# ArduinoMegaShield2.net
KiCad netlist of a schematic drawn in EAGLE
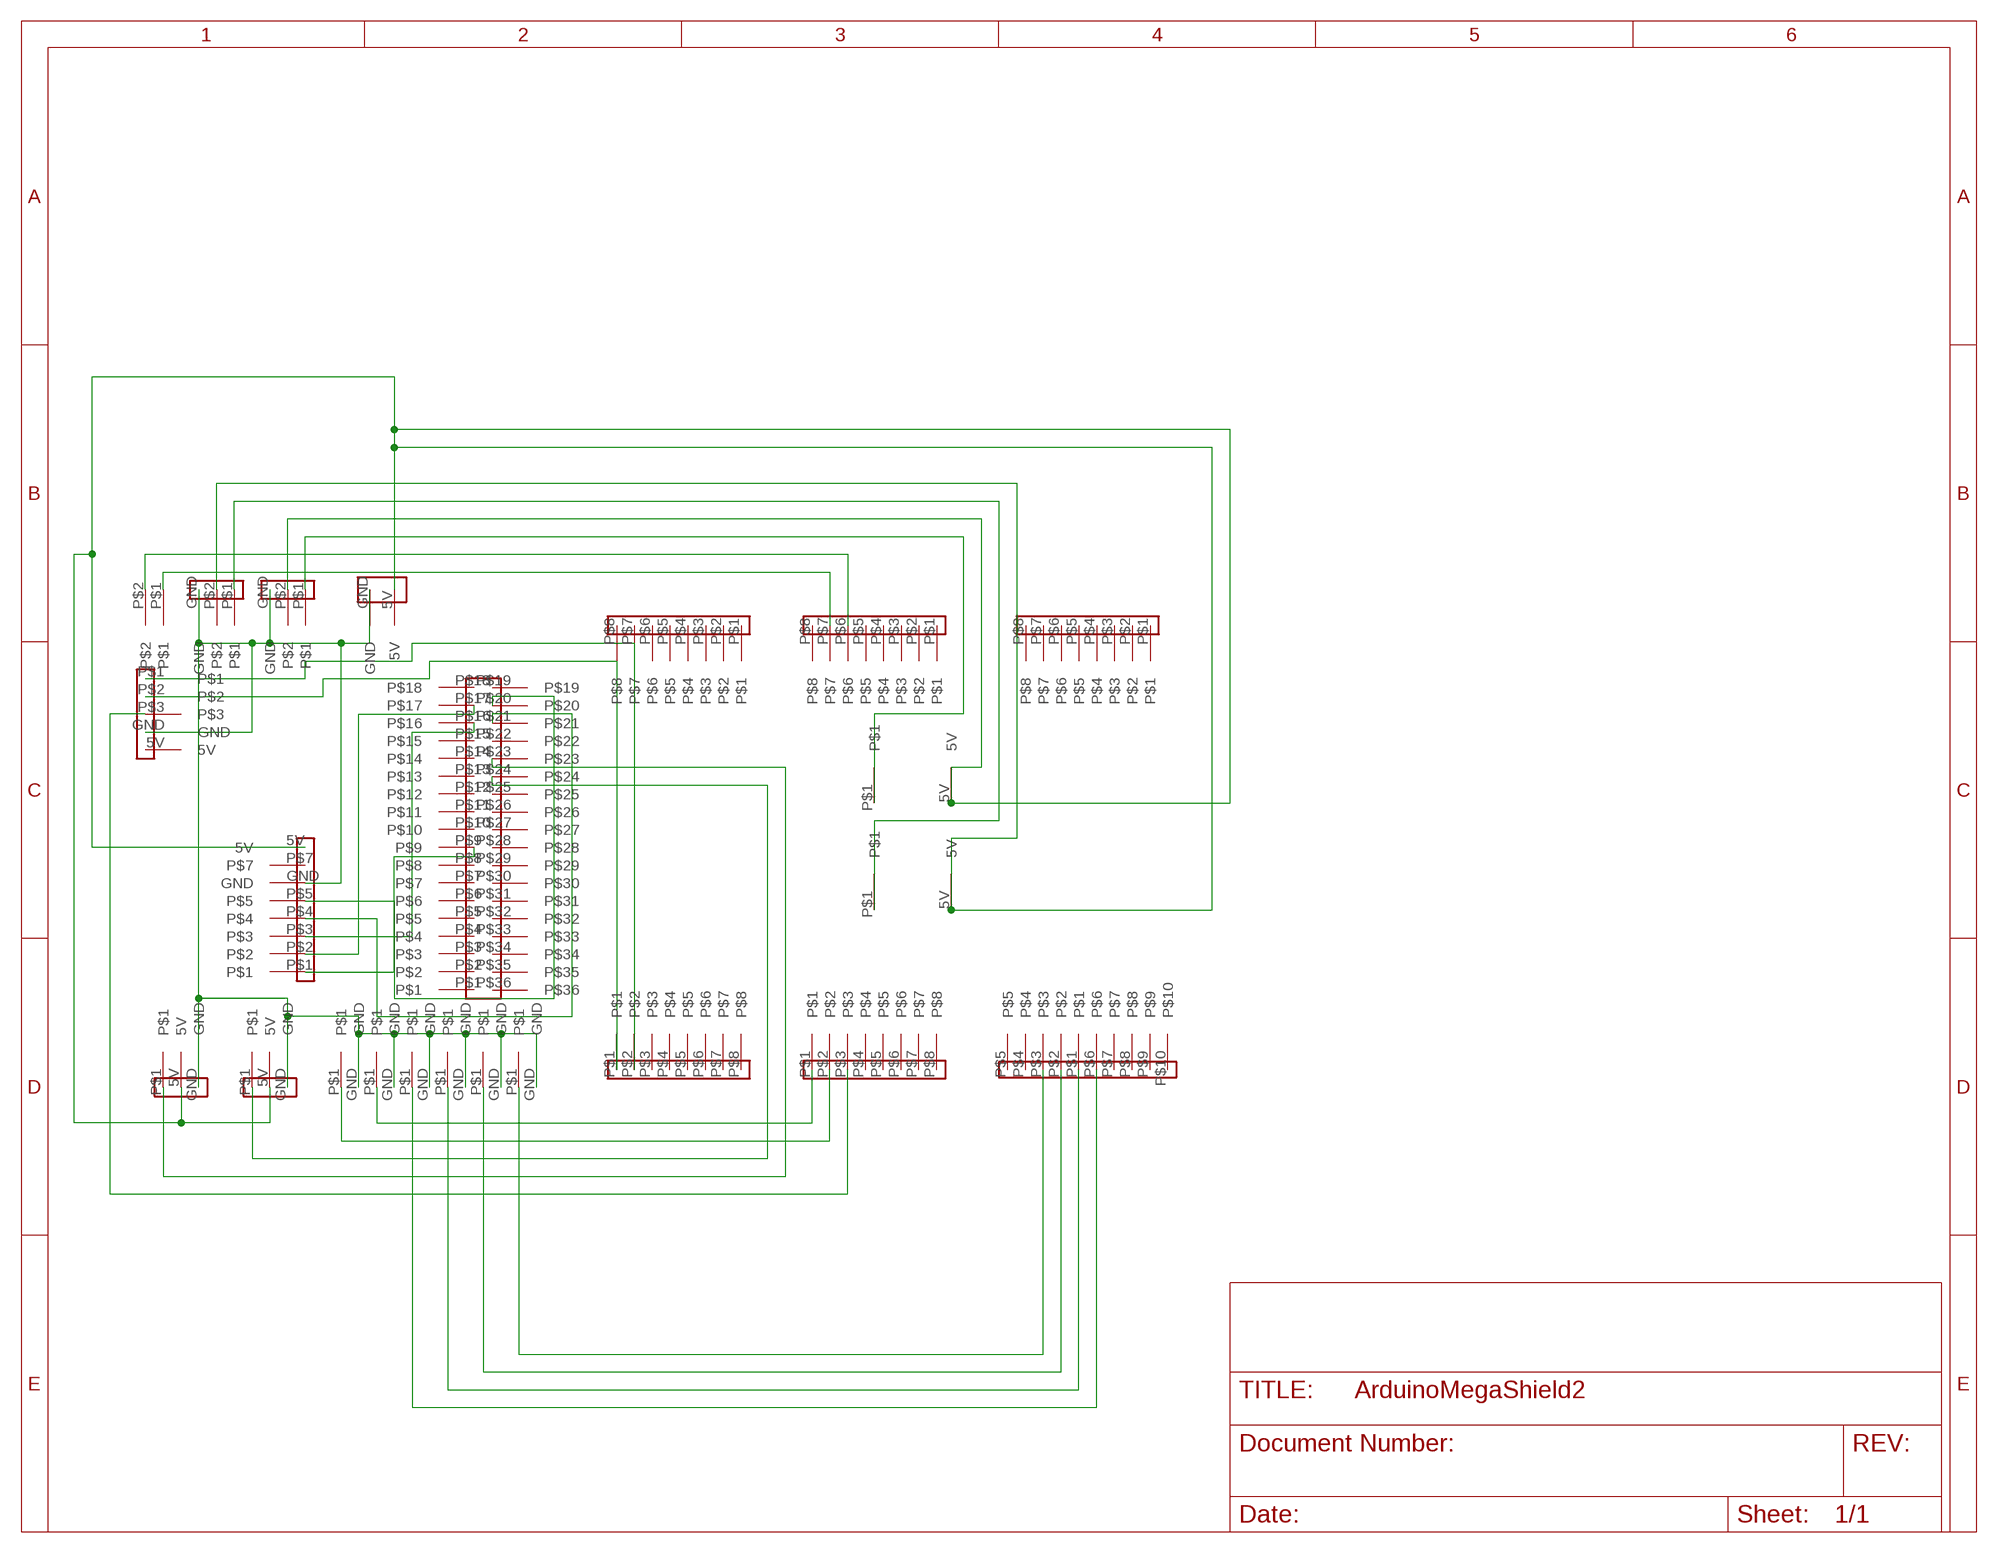
[diagram p0: schematic, sheet 1]

(export (version "E")
  (design (tool "Eeschema 10.0.6"))
  (components
    (comp (ref "U$1")
      (value "8PINHEADER2.54MM")
      (footprint "eagle-import:8PINHEADER2.54MM")
      (libsource (lib "eagle-import") (part "8PINHEADER2.54MM"))
    )
    (comp (ref "U$2")
      (value "8PINHEADER2.54MM")
      (footprint "eagle-import:8PINHEADER2.54MM")
      (libsource (lib "eagle-import") (part "8PINHEADER2.54MM"))
    )
    (comp (ref "U$3")
      (value "8PINHEADER2.54MM")
      (footprint "eagle-import:8PINHEADER2.54MM")
      (libsource (lib "eagle-import") (part "8PINHEADER2.54MM"))
    )
    (comp (ref "U$4")
      (value "8PINHEADER2.54MM")
      (footprint "eagle-import:8PINHEADER2.54MM")
      (libsource (lib "eagle-import") (part "8PINHEADER2.54MM"))
    )
    (comp (ref "U$5")
      (value "8PINHEADER2.54MM")
      (footprint "eagle-import:8PINHEADER2.54MM")
      (libsource (lib "eagle-import") (part "8PINHEADER2.54MM"))
    )
    (comp (ref "U$6")
      (value "10PINHEADER2.54MM")
      (footprint "eagle-import:10PINHEADER2.54MM")
      (libsource (lib "eagle-import") (part "10PINHEADER2.54MM"))
    )
    (comp (ref "U$7")
      (value "18X2HEADER2.54MM")
      (footprint "eagle-import:18X2HEADER2.54MM")
      (libsource (lib "eagle-import") (part "18X2HEADER2.54MM"))
    )
    (comp (ref "U$8")
      (value "5PINHEADER2.54MM")
      (footprint "eagle-import:5PINHEADER2.54MM")
      (libsource (lib "eagle-import") (part "5PINHEADER2.54MM"))
    )
    (comp (ref "U$9")
      (value "SERVOS")
      (footprint "eagle-import:SERVOS")
      (libsource (lib "eagle-import") (part "SERVOS"))
    )
    (comp (ref "U$10")
      (value "SDCARDMODULE")
      (footprint "eagle-import:SDCARDMODULE")
      (libsource (lib "eagle-import") (part "SDCARDMODULE"))
    )
    (comp (ref "U$11")
      (value "SERVOS")
      (footprint "eagle-import:SERVOS")
      (libsource (lib "eagle-import") (part "SERVOS"))
    )
    (comp (ref "U$12")
      (value "HALLEFFECTSENSORS")
      (footprint "eagle-import:HALLEFFECTSENSORS")
      (libsource (lib "eagle-import") (part "HALLEFFECTSENSORS"))
    )
    (comp (ref "U$13")
      (value "HALLEFFECTSENSORS")
      (footprint "eagle-import:HALLEFFECTSENSORS")
      (libsource (lib "eagle-import") (part "HALLEFFECTSENSORS"))
    )
    (comp (ref "U$14")
      (value "2PIN2.54MM")
      (footprint "eagle-import:2PIN2.54MM")
      (libsource (lib "eagle-import") (part "2PIN2.54MM"))
    )
    (comp (ref "U$15")
      (value "2PIN2.54MM")
      (footprint "eagle-import:2PIN2.54MM")
      (libsource (lib "eagle-import") (part "2PIN2.54MM"))
    )
    (comp (ref "U$16")
      (value "2PIN2.54MM")
      (footprint "eagle-import:2PIN2.54MM")
      (libsource (lib "eagle-import") (part "2PIN2.54MM"))
    )
    (comp (ref "U$17")
      (value "2PIN2.54MM")
      (footprint "eagle-import:2PIN2.54MM")
      (libsource (lib "eagle-import") (part "2PIN2.54MM"))
    )
    (comp (ref "U$18")
      (value "2PIN2.54MM")
      (footprint "eagle-import:2PIN2.54MM")
      (libsource (lib "eagle-import") (part "2PIN2.54MM"))
    )
    (comp (ref "U$19")
      (value "2PIN2.54MM")
      (footprint "eagle-import:2PIN2.54MM")
      (libsource (lib "eagle-import") (part "2PIN2.54MM"))
    )
    (comp (ref "U$20")
      (value "2PIN11MM")
      (footprint "eagle-import:2PIN11MM")
      (libsource (lib "eagle-import") (part "2PIN11MM"))
    )
    (comp (ref "U$21")
      (value "2PIN11MM")
      (footprint "eagle-import:2PIN11MM")
      (libsource (lib "eagle-import") (part "2PIN11MM"))
    )
    (comp (ref "U$22")
      (value "BUTTONS")
      (footprint "eagle-import:BUTTONS")
      (libsource (lib "eagle-import") (part "BUTTONS"))
    )
    (comp (ref "U$23")
      (value "2PINTERMINAL3.5MM")
      (footprint "eagle-import:2PINTERMINAL3.5MM")
      (libsource (lib "eagle-import") (part "2PINTERMINAL3.5MM"))
    )
  )
  (nets
    (net (code "1") (name "Net-(U$1-PadP$1)") (class "Default")
      (node (ref "U$1") (pin "P$1") (pinfunction "P$1_P$1") (pintype "bidirectional"))
      (node (ref "U$15") (pin "P$1") (pinfunction "P$1_P$1") (pintype "bidirectional"))
    )
    (net (code "2") (name "Net-(U$1-PadP$2)") (class "Default")
      (node (ref "U$1") (pin "P$2") (pinfunction "P$2_P$2") (pintype "bidirectional"))
      (node (ref "U$14") (pin "P$1") (pinfunction "P$1_P$1") (pintype "bidirectional"))
    )
    (net (code "3") (name "Net-(U$1-PadP$3)") (class "Default")
      (node (ref "U$1") (pin "P$3") (pinfunction "P$3_P$3") (pintype "bidirectional"))
      (node (ref "U$8") (pin "P$3") (pinfunction "P$3_P$3") (pintype "bidirectional"))
    )
    (net (code "4") (name "Net-(U$2-PadP$1)") (class "Default")
      (node (ref "U$2") (pin "P$1") (pinfunction "P$1_P$1") (pintype "bidirectional"))
      (node (ref "U$8") (pin "P$2") (pinfunction "P$2_P$2") (pintype "bidirectional"))
    )
    (net (code "5") (name "Net-(U$2-PadP$2)") (class "Default")
      (node (ref "U$2") (pin "P$2") (pinfunction "P$2_P$2") (pintype "bidirectional"))
      (node (ref "U$8") (pin "P$1") (pinfunction "P$1_P$1") (pintype "bidirectional"))
    )
    (net (code "6") (name "Net-(U$7-PadP$23)") (class "Default")
      (node (ref "U$7") (pin "P$23") (pinfunction "P$23_P$23") (pintype "bidirectional"))
      (node (ref "U$9") (pin "P$1") (pinfunction "P$1_P$1") (pintype "bidirectional"))
    )
    (net (code "7") (name "Net-(U$10-Pad5V)") (class "Default")
      (node (ref "U$10") (pin "5V") (pinfunction "5V_5V") (pintype "bidirectional"))
      (node (ref "U$11") (pin "5V") (pinfunction "5V_5V") (pintype "bidirectional"))
      (node (ref "U$12") (pin "P$2") (pinfunction "P$2_P$2") (pintype "bidirectional"))
      (node (ref "U$13") (pin "P$2") (pinfunction "P$2_P$2") (pintype "bidirectional"))
      (node (ref "U$20") (pin "5V") (pinfunction "5V_5V") (pintype "bidirectional"))
      (node (ref "U$21") (pin "5V") (pinfunction "5V_5V") (pintype "bidirectional"))
      (node (ref "U$23") (pin "5V") (pinfunction "5V_5V") (pintype "bidirectional"))
      (node (ref "U$9") (pin "5V") (pinfunction "5V_5V") (pintype "bidirectional"))
    )
    (net (code "8") (name "Net-(U$10-PadGND)") (class "Default")
      (node (ref "U$10") (pin "GND") (pinfunction "GND_GND") (pintype "bidirectional"))
      (node (ref "U$11") (pin "GND") (pinfunction "GND_GND") (pintype "bidirectional"))
      (node (ref "U$12") (pin "GND") (pinfunction "GND_GND") (pintype "bidirectional"))
      (node (ref "U$13") (pin "GND") (pinfunction "GND_GND") (pintype "bidirectional"))
      (node (ref "U$14") (pin "GND") (pinfunction "GND_GND") (pintype "bidirectional"))
      (node (ref "U$15") (pin "GND") (pinfunction "GND_GND") (pintype "bidirectional"))
      (node (ref "U$16") (pin "GND") (pinfunction "GND_GND") (pintype "bidirectional"))
      (node (ref "U$17") (pin "GND") (pinfunction "GND_GND") (pintype "bidirectional"))
      (node (ref "U$18") (pin "GND") (pinfunction "GND_GND") (pintype "bidirectional"))
      (node (ref "U$19") (pin "GND") (pinfunction "GND_GND") (pintype "bidirectional"))
      (node (ref "U$23") (pin "GND") (pinfunction "GND_GND") (pintype "bidirectional"))
      (node (ref "U$8") (pin "GND") (pinfunction "GND_GND") (pintype "bidirectional"))
      (node (ref "U$9") (pin "GND") (pinfunction "GND_GND") (pintype "bidirectional"))
    )
    (net (code "9") (name "Net-(U$10-PadP$1)") (class "Default")
      (node (ref "U$10") (pin "P$1") (pinfunction "P$1_P$1") (pintype "bidirectional"))
      (node (ref "U$7") (pin "P$9") (pinfunction "P$9_P$9") (pintype "bidirectional"))
    )
    (net (code "10") (name "Net-(U$10-PadP$2)") (class "Default")
      (node (ref "U$10") (pin "P$2") (pinfunction "P$2_P$2") (pintype "bidirectional"))
      (node (ref "U$7") (pin "P$17") (pinfunction "P$17_P$17") (pintype "bidirectional"))
    )
    (net (code "11") (name "Net-(U$10-PadP$3)") (class "Default")
      (node (ref "U$10") (pin "P$3") (pinfunction "P$3_P$3") (pintype "bidirectional"))
      (node (ref "U$7") (pin "P$16") (pinfunction "P$16_P$16") (pintype "bidirectional"))
    )
    (net (code "12") (name "Net-(U$10-PadP$4)") (class "Default")
      (node (ref "U$10") (pin "P$4") (pinfunction "P$4_P$4") (pintype "bidirectional"))
      (node (ref "U$7") (pin "P$21") (pinfunction "P$21_P$21") (pintype "bidirectional"))
    )
    (net (code "13") (name "Net-(U$10-PadP$5)") (class "Default")
      (node (ref "U$10") (pin "P$5") (pinfunction "P$5_P$5") (pintype "bidirectional"))
      (node (ref "U$7") (pin "P$20") (pinfunction "P$20_P$20") (pintype "bidirectional"))
    )
    (net (code "14") (name "Net-(U$11-PadP$1)") (class "Default")
      (node (ref "U$11") (pin "P$1") (pinfunction "P$1_P$1") (pintype "bidirectional"))
      (node (ref "U$7") (pin "P$24") (pinfunction "P$24_P$24") (pintype "bidirectional"))
    )
    (net (code "15") (name "Net-(U$12-PadP$1)") (class "Default")
      (node (ref "U$12") (pin "P$1") (pinfunction "P$1_P$1") (pintype "bidirectional"))
      (node (ref "U$21") (pin "P$1") (pinfunction "P$1_P$1") (pintype "bidirectional"))
    )
    (net (code "16") (name "Net-(U$13-PadP$1)") (class "Default")
      (node (ref "U$13") (pin "P$1") (pinfunction "P$1_P$1") (pintype "bidirectional"))
      (node (ref "U$20") (pin "P$1") (pinfunction "P$1_P$1") (pintype "bidirectional"))
    )
    (net (code "17") (name "Net-(U$16-PadP$1)") (class "Default")
      (node (ref "U$16") (pin "P$1") (pinfunction "P$1_P$1") (pintype "bidirectional"))
      (node (ref "U$6") (pin "P$6") (pinfunction "P$6_P$6") (pintype "bidirectional"))
    )
    (net (code "18") (name "Net-(U$17-PadP$1)") (class "Default")
      (node (ref "U$17") (pin "P$1") (pinfunction "P$1_P$1") (pintype "bidirectional"))
      (node (ref "U$6") (pin "P$1") (pinfunction "P$1_P$1") (pintype "bidirectional"))
    )
    (net (code "19") (name "Net-(U$18-PadP$1)") (class "Default")
      (node (ref "U$18") (pin "P$1") (pinfunction "P$1_P$1") (pintype "bidirectional"))
      (node (ref "U$6") (pin "P$2") (pinfunction "P$2_P$2") (pintype "bidirectional"))
    )
    (net (code "20") (name "Net-(U$19-PadP$1)") (class "Default")
      (node (ref "U$19") (pin "P$1") (pinfunction "P$1_P$1") (pintype "bidirectional"))
      (node (ref "U$6") (pin "P$3") (pinfunction "P$3_P$3") (pintype "bidirectional"))
    )
    (net (code "21") (name "Net-(U$22-PadP$1)") (class "Default")
      (node (ref "U$22") (pin "P$1") (pinfunction "P$1_P$1") (pintype "bidirectional"))
      (node (ref "U$4") (pin "P$7") (pinfunction "P$7_P$7") (pintype "bidirectional"))
    )
    (net (code "22") (name "Net-(U$22-PadP$2)") (class "Default")
      (node (ref "U$22") (pin "P$2") (pinfunction "P$2_P$2") (pintype "bidirectional"))
      (node (ref "U$4") (pin "P$6") (pinfunction "P$6_P$6") (pintype "bidirectional"))
    )
    (net (code "23") (name "unconnected-(U$1-PadP$4)") (class "Default")
      (node (ref "U$1") (pin "P$4") (pinfunction "P$4_P$4") (pintype "bidirectional"))
    )
    (net (code "24") (name "unconnected-(U$1-PadP$5)") (class "Default")
      (node (ref "U$1") (pin "P$5") (pinfunction "P$5_P$5") (pintype "bidirectional"))
    )
    (net (code "25") (name "unconnected-(U$1-PadP$6)") (class "Default")
      (node (ref "U$1") (pin "P$6") (pinfunction "P$6_P$6") (pintype "bidirectional"))
    )
    (net (code "26") (name "unconnected-(U$1-PadP$7)") (class "Default")
      (node (ref "U$1") (pin "P$7") (pinfunction "P$7_P$7") (pintype "bidirectional"))
    )
    (net (code "27") (name "unconnected-(U$1-PadP$8)") (class "Default")
      (node (ref "U$1") (pin "P$8") (pinfunction "P$8_P$8") (pintype "bidirectional"))
    )
    (net (code "28") (name "unconnected-(U$2-PadP$3)") (class "Default")
      (node (ref "U$2") (pin "P$3") (pinfunction "P$3_P$3") (pintype "bidirectional"))
    )
    (net (code "29") (name "unconnected-(U$2-PadP$4)") (class "Default")
      (node (ref "U$2") (pin "P$4") (pinfunction "P$4_P$4") (pintype "bidirectional"))
    )
    (net (code "30") (name "unconnected-(U$2-PadP$5)") (class "Default")
      (node (ref "U$2") (pin "P$5") (pinfunction "P$5_P$5") (pintype "bidirectional"))
    )
    (net (code "31") (name "unconnected-(U$2-PadP$6)") (class "Default")
      (node (ref "U$2") (pin "P$6") (pinfunction "P$6_P$6") (pintype "bidirectional"))
    )
    (net (code "32") (name "unconnected-(U$2-PadP$7)") (class "Default")
      (node (ref "U$2") (pin "P$7") (pinfunction "P$7_P$7") (pintype "bidirectional"))
    )
    (net (code "33") (name "unconnected-(U$2-PadP$8)") (class "Default")
      (node (ref "U$2") (pin "P$8") (pinfunction "P$8_P$8") (pintype "bidirectional"))
    )
    (net (code "34") (name "unconnected-(U$3-PadP$1)") (class "Default")
      (node (ref "U$3") (pin "P$1") (pinfunction "P$1_P$1") (pintype "bidirectional"))
    )
    (net (code "35") (name "unconnected-(U$3-PadP$2)") (class "Default")
      (node (ref "U$3") (pin "P$2") (pinfunction "P$2_P$2") (pintype "bidirectional"))
    )
    (net (code "36") (name "unconnected-(U$3-PadP$3)") (class "Default")
      (node (ref "U$3") (pin "P$3") (pinfunction "P$3_P$3") (pintype "bidirectional"))
    )
    (net (code "37") (name "unconnected-(U$3-PadP$4)") (class "Default")
      (node (ref "U$3") (pin "P$4") (pinfunction "P$4_P$4") (pintype "bidirectional"))
    )
    (net (code "38") (name "unconnected-(U$3-PadP$5)") (class "Default")
      (node (ref "U$3") (pin "P$5") (pinfunction "P$5_P$5") (pintype "bidirectional"))
    )
    (net (code "39") (name "unconnected-(U$3-PadP$6)") (class "Default")
      (node (ref "U$3") (pin "P$6") (pinfunction "P$6_P$6") (pintype "bidirectional"))
    )
    (net (code "40") (name "unconnected-(U$3-PadP$7)") (class "Default")
      (node (ref "U$3") (pin "P$7") (pinfunction "P$7_P$7") (pintype "bidirectional"))
    )
    (net (code "41") (name "unconnected-(U$3-PadP$8)") (class "Default")
      (node (ref "U$3") (pin "P$8") (pinfunction "P$8_P$8") (pintype "bidirectional"))
    )
    (net (code "42") (name "unconnected-(U$4-PadP$1)") (class "Default")
      (node (ref "U$4") (pin "P$1") (pinfunction "P$1_P$1") (pintype "bidirectional"))
    )
    (net (code "43") (name "unconnected-(U$4-PadP$2)") (class "Default")
      (node (ref "U$4") (pin "P$2") (pinfunction "P$2_P$2") (pintype "bidirectional"))
    )
    (net (code "44") (name "unconnected-(U$4-PadP$3)") (class "Default")
      (node (ref "U$4") (pin "P$3") (pinfunction "P$3_P$3") (pintype "bidirectional"))
    )
    (net (code "45") (name "unconnected-(U$4-PadP$4)") (class "Default")
      (node (ref "U$4") (pin "P$4") (pinfunction "P$4_P$4") (pintype "bidirectional"))
    )
    (net (code "46") (name "unconnected-(U$4-PadP$5)") (class "Default")
      (node (ref "U$4") (pin "P$5") (pinfunction "P$5_P$5") (pintype "bidirectional"))
    )
    (net (code "47") (name "unconnected-(U$4-PadP$8)") (class "Default")
      (node (ref "U$4") (pin "P$8") (pinfunction "P$8_P$8") (pintype "bidirectional"))
    )
    (net (code "48") (name "unconnected-(U$5-PadP$1)") (class "Default")
      (node (ref "U$5") (pin "P$1") (pinfunction "P$1_P$1") (pintype "bidirectional"))
    )
    (net (code "49") (name "unconnected-(U$5-PadP$2)") (class "Default")
      (node (ref "U$5") (pin "P$2") (pinfunction "P$2_P$2") (pintype "bidirectional"))
    )
    (net (code "50") (name "unconnected-(U$5-PadP$3)") (class "Default")
      (node (ref "U$5") (pin "P$3") (pinfunction "P$3_P$3") (pintype "bidirectional"))
    )
    (net (code "51") (name "unconnected-(U$5-PadP$4)") (class "Default")
      (node (ref "U$5") (pin "P$4") (pinfunction "P$4_P$4") (pintype "bidirectional"))
    )
    (net (code "52") (name "unconnected-(U$5-PadP$5)") (class "Default")
      (node (ref "U$5") (pin "P$5") (pinfunction "P$5_P$5") (pintype "bidirectional"))
    )
    (net (code "53") (name "unconnected-(U$5-PadP$6)") (class "Default")
      (node (ref "U$5") (pin "P$6") (pinfunction "P$6_P$6") (pintype "bidirectional"))
    )
    (net (code "54") (name "unconnected-(U$5-PadP$7)") (class "Default")
      (node (ref "U$5") (pin "P$7") (pinfunction "P$7_P$7") (pintype "bidirectional"))
    )
    (net (code "55") (name "unconnected-(U$5-PadP$8)") (class "Default")
      (node (ref "U$5") (pin "P$8") (pinfunction "P$8_P$8") (pintype "bidirectional"))
    )
    (net (code "56") (name "unconnected-(U$6-PadP$4)") (class "Default")
      (node (ref "U$6") (pin "P$4") (pinfunction "P$4_P$4") (pintype "bidirectional"))
    )
    (net (code "57") (name "unconnected-(U$6-PadP$5)") (class "Default")
      (node (ref "U$6") (pin "P$5") (pinfunction "P$5_P$5") (pintype "bidirectional"))
    )
    (net (code "58") (name "unconnected-(U$6-PadP$7)") (class "Default")
      (node (ref "U$6") (pin "P$7") (pinfunction "P$7_P$7") (pintype "bidirectional"))
    )
    (net (code "59") (name "unconnected-(U$6-PadP$8)") (class "Default")
      (node (ref "U$6") (pin "P$8") (pinfunction "P$8_P$8") (pintype "bidirectional"))
    )
    (net (code "60") (name "unconnected-(U$6-PadP$9)") (class "Default")
      (node (ref "U$6") (pin "P$9") (pinfunction "P$9_P$9") (pintype "bidirectional"))
    )
    (net (code "61") (name "unconnected-(U$6-PadP$10)") (class "Default")
      (node (ref "U$6") (pin "P$10") (pinfunction "P$10_P$10") (pintype "bidirectional"))
    )
    (net (code "62") (name "unconnected-(U$7-PadP$1)") (class "Default")
      (node (ref "U$7") (pin "P$1") (pinfunction "P$1_P$1") (pintype "bidirectional"))
    )
    (net (code "63") (name "unconnected-(U$7-PadP$2)") (class "Default")
      (node (ref "U$7") (pin "P$2") (pinfunction "P$2_P$2") (pintype "bidirectional"))
    )
    (net (code "64") (name "unconnected-(U$7-PadP$3)") (class "Default")
      (node (ref "U$7") (pin "P$3") (pinfunction "P$3_P$3") (pintype "bidirectional"))
    )
    (net (code "65") (name "unconnected-(U$7-PadP$4)") (class "Default")
      (node (ref "U$7") (pin "P$4") (pinfunction "P$4_P$4") (pintype "bidirectional"))
    )
    (net (code "66") (name "unconnected-(U$7-PadP$5)") (class "Default")
      (node (ref "U$7") (pin "P$5") (pinfunction "P$5_P$5") (pintype "bidirectional"))
    )
    (net (code "67") (name "unconnected-(U$7-PadP$6)") (class "Default")
      (node (ref "U$7") (pin "P$6") (pinfunction "P$6_P$6") (pintype "bidirectional"))
    )
    (net (code "68") (name "unconnected-(U$7-PadP$7)") (class "Default")
      (node (ref "U$7") (pin "P$7") (pinfunction "P$7_P$7") (pintype "bidirectional"))
    )
    (net (code "69") (name "unconnected-(U$7-PadP$8)") (class "Default")
      (node (ref "U$7") (pin "P$8") (pinfunction "P$8_P$8") (pintype "bidirectional"))
    )
    (net (code "70") (name "unconnected-(U$7-PadP$10)") (class "Default")
      (node (ref "U$7") (pin "P$10") (pinfunction "P$10_P$10") (pintype "bidirectional"))
    )
    (net (code "71") (name "unconnected-(U$7-PadP$11)") (class "Default")
      (node (ref "U$7") (pin "P$11") (pinfunction "P$11_P$11") (pintype "bidirectional"))
    )
    (net (code "72") (name "unconnected-(U$7-PadP$12)") (class "Default")
      (node (ref "U$7") (pin "P$12") (pinfunction "P$12_P$12") (pintype "bidirectional"))
    )
    (net (code "73") (name "unconnected-(U$7-PadP$13)") (class "Default")
      (node (ref "U$7") (pin "P$13") (pinfunction "P$13_P$13") (pintype "bidirectional"))
    )
    (net (code "74") (name "unconnected-(U$7-PadP$14)") (class "Default")
      (node (ref "U$7") (pin "P$14") (pinfunction "P$14_P$14") (pintype "bidirectional"))
    )
    (net (code "75") (name "unconnected-(U$7-PadP$15)") (class "Default")
      (node (ref "U$7") (pin "P$15") (pinfunction "P$15_P$15") (pintype "bidirectional"))
    )
    (net (code "76") (name "unconnected-(U$7-PadP$18)") (class "Default")
      (node (ref "U$7") (pin "P$18") (pinfunction "P$18_P$18") (pintype "bidirectional"))
    )
    (net (code "77") (name "unconnected-(U$7-PadP$19)") (class "Default")
      (node (ref "U$7") (pin "P$19") (pinfunction "P$19_P$19") (pintype "bidirectional"))
    )
    (net (code "78") (name "unconnected-(U$7-PadP$22)") (class "Default")
      (node (ref "U$7") (pin "P$22") (pinfunction "P$22_P$22") (pintype "bidirectional"))
    )
    (net (code "79") (name "unconnected-(U$7-PadP$25)") (class "Default")
      (node (ref "U$7") (pin "P$25") (pinfunction "P$25_P$25") (pintype "bidirectional"))
    )
    (net (code "80") (name "unconnected-(U$7-PadP$26)") (class "Default")
      (node (ref "U$7") (pin "P$26") (pinfunction "P$26_P$26") (pintype "bidirectional"))
    )
    (net (code "81") (name "unconnected-(U$7-PadP$27)") (class "Default")
      (node (ref "U$7") (pin "P$27") (pinfunction "P$27_P$27") (pintype "bidirectional"))
    )
    (net (code "82") (name "unconnected-(U$7-PadP$28)") (class "Default")
      (node (ref "U$7") (pin "P$28") (pinfunction "P$28_P$28") (pintype "bidirectional"))
    )
    (net (code "83") (name "unconnected-(U$7-PadP$29)") (class "Default")
      (node (ref "U$7") (pin "P$29") (pinfunction "P$29_P$29") (pintype "bidirectional"))
    )
    (net (code "84") (name "unconnected-(U$7-PadP$30)") (class "Default")
      (node (ref "U$7") (pin "P$30") (pinfunction "P$30_P$30") (pintype "bidirectional"))
    )
    (net (code "85") (name "unconnected-(U$7-PadP$31)") (class "Default")
      (node (ref "U$7") (pin "P$31") (pinfunction "P$31_P$31") (pintype "bidirectional"))
    )
    (net (code "86") (name "unconnected-(U$7-PadP$32)") (class "Default")
      (node (ref "U$7") (pin "P$32") (pinfunction "P$32_P$32") (pintype "bidirectional"))
    )
    (net (code "87") (name "unconnected-(U$7-PadP$33)") (class "Default")
      (node (ref "U$7") (pin "P$33") (pinfunction "P$33_P$33") (pintype "bidirectional"))
    )
    (net (code "88") (name "unconnected-(U$7-PadP$34)") (class "Default")
      (node (ref "U$7") (pin "P$34") (pinfunction "P$34_P$34") (pintype "bidirectional"))
    )
    (net (code "89") (name "unconnected-(U$7-PadP$35)") (class "Default")
      (node (ref "U$7") (pin "P$35") (pinfunction "P$35_P$35") (pintype "bidirectional"))
    )
    (net (code "90") (name "unconnected-(U$7-PadP$36)") (class "Default")
      (node (ref "U$7") (pin "P$36") (pinfunction "P$36_P$36") (pintype "bidirectional"))
    )
    (net (code "91") (name "unconnected-(U$8-Pad5V)") (class "Default")
      (node (ref "U$8") (pin "5V") (pinfunction "5V_5V") (pintype "bidirectional"))
    )
    (net (code "92") (name "unconnected-(U$10-PadP$7)") (class "Default")
      (node (ref "U$10") (pin "P$7") (pinfunction "P$7_P$7") (pintype "bidirectional"))
    )
  )
)
